# TriDrone_2012.net
KiCad netlist of a schematic drawn in EAGLE
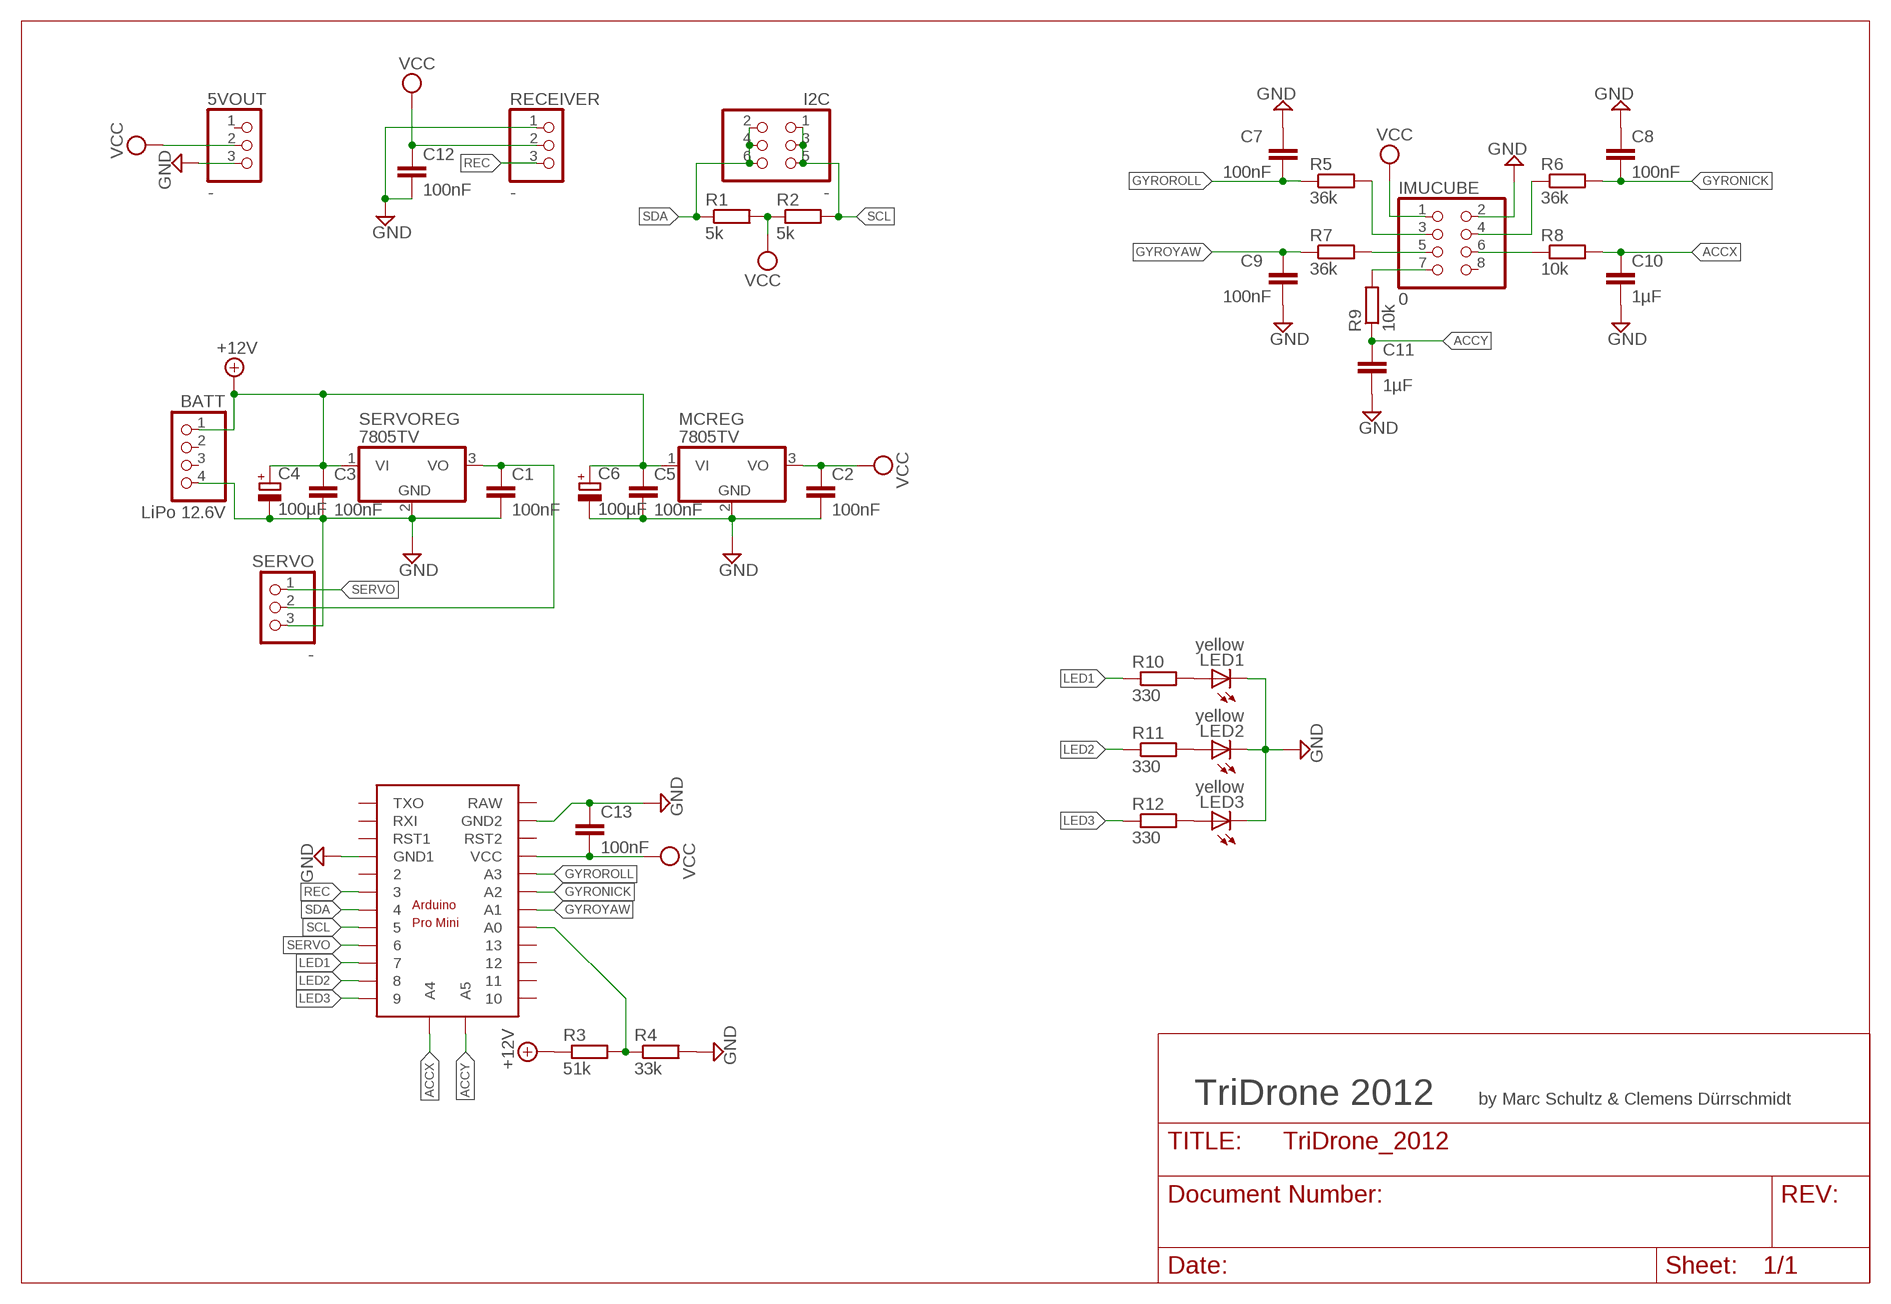
[diagram p0: schematic, sheet 1]

(export (version "E")
  (design (tool "Eeschema 10.0.6"))
  (components
    (comp (ref "5VOUT")
      (value "-")
      (footprint "eagle-import:1X03")
      (libsource (lib "eagle-import") (part "PINHD-1X3"))
    )
    (comp (ref "BATT")
      (value "LiPo 12.6V")
      (footprint "eagle-import:1X04_90")
      (libsource (lib "eagle-import") (part "PINHD-1X4/90"))
    )
    (comp (ref "C1")
      (value "100nF")
      (footprint "eagle-import:C025-025X050")
      (libsource (lib "eagle-import") (part "C-EU025-025X050"))
    )
    (comp (ref "C2")
      (value "100nF")
      (footprint "eagle-import:C025-025X050")
      (libsource (lib "eagle-import") (part "C-EU025-025X050"))
    )
    (comp (ref "C3")
      (value "100nF")
      (footprint "eagle-import:C025-025X050")
      (libsource (lib "eagle-import") (part "C-EU025-025X050"))
    )
    (comp (ref "C4")
      (value "100µF")
      (footprint "eagle-import:E2,5-7")
      (libsource (lib "eagle-import") (part "CPOL-EUE2.5-7"))
    )
    (comp (ref "C5")
      (value "100nF")
      (footprint "eagle-import:C025-025X050")
      (libsource (lib "eagle-import") (part "C-EU025-025X050"))
    )
    (comp (ref "C6")
      (value "100µF")
      (footprint "eagle-import:E2,5-7")
      (libsource (lib "eagle-import") (part "CPOL-EUE2.5-7"))
    )
    (comp (ref "C7")
      (value "100nF")
      (footprint "eagle-import:C025-025X050")
      (libsource (lib "eagle-import") (part "C-EU025-025X050"))
    )
    (comp (ref "C8")
      (value "100nF")
      (footprint "eagle-import:C025-025X050")
      (libsource (lib "eagle-import") (part "C-EU025-025X050"))
    )
    (comp (ref "C9")
      (value "100nF")
      (footprint "eagle-import:C025-025X050")
      (libsource (lib "eagle-import") (part "C-EU025-025X050"))
    )
    (comp (ref "C10")
      (value "1µF")
      (footprint "eagle-import:C025-025X050")
      (libsource (lib "eagle-import") (part "C-EU025-025X050"))
    )
    (comp (ref "C11")
      (value "1µF")
      (footprint "eagle-import:C025-025X050")
      (libsource (lib "eagle-import") (part "C-EU025-025X050"))
    )
    (comp (ref "C12")
      (value "100nF")
      (footprint "eagle-import:C025-025X050")
      (libsource (lib "eagle-import") (part "C-EU025-025X050"))
    )
    (comp (ref "C13")
      (value "100nF")
      (footprint "eagle-import:C025-025X050")
      (libsource (lib "eagle-import") (part "C-EU025-025X050"))
    )
    (comp (ref "I2C")
      (value "-")
      (footprint "eagle-import:2X03_90")
      (libsource (lib "eagle-import") (part "PINHD-2X3/90"))
    )
    (comp (ref "IMUCUBE")
      (value "0")
      (footprint "eagle-import:2X04")
      (libsource (lib "eagle-import") (part "PINHD-2X4"))
    )
    (comp (ref "LED1")
      (value "yellow")
      (footprint "eagle-import:LED3MM")
      (libsource (lib "eagle-import") (part "LED3MM"))
    )
    (comp (ref "LED2")
      (value "yellow")
      (footprint "eagle-import:LED3MM")
      (libsource (lib "eagle-import") (part "LED3MM"))
    )
    (comp (ref "LED3")
      (value "yellow")
      (footprint "eagle-import:LED3MM")
      (libsource (lib "eagle-import") (part "LED3MM"))
    )
    (comp (ref "MCREG")
      (value "7805TV")
      (footprint "eagle-import:TO220V")
      (libsource (lib "eagle-import") (part "78TV05"))
    )
    (comp (ref "R1")
      (value "5k")
      (footprint "eagle-import:0204_7")
      (libsource (lib "eagle-import") (part "R-EU_0204/7"))
    )
    (comp (ref "R2")
      (value "5k")
      (footprint "eagle-import:0204_7")
      (libsource (lib "eagle-import") (part "R-EU_0204/7"))
    )
    (comp (ref "R3")
      (value "51k")
      (footprint "eagle-import:0204_7")
      (libsource (lib "eagle-import") (part "R-EU_0204/7"))
    )
    (comp (ref "R4")
      (value "33k")
      (footprint "eagle-import:0204_7")
      (libsource (lib "eagle-import") (part "R-EU_0204/7"))
    )
    (comp (ref "R5")
      (value "36k")
      (footprint "eagle-import:0204_7")
      (libsource (lib "eagle-import") (part "R-EU_0204/7"))
    )
    (comp (ref "R6")
      (value "36k")
      (footprint "eagle-import:0204_7")
      (libsource (lib "eagle-import") (part "R-EU_0204/7"))
    )
    (comp (ref "R7")
      (value "36k")
      (footprint "eagle-import:0204_7")
      (libsource (lib "eagle-import") (part "R-EU_0204/7"))
    )
    (comp (ref "R8")
      (value "10k")
      (footprint "eagle-import:0204_7")
      (libsource (lib "eagle-import") (part "R-EU_0204/7"))
    )
    (comp (ref "R9")
      (value "10k")
      (footprint "eagle-import:0204_7")
      (libsource (lib "eagle-import") (part "R-EU_0204/7"))
    )
    (comp (ref "R10")
      (value "330")
      (footprint "eagle-import:0204_7")
      (libsource (lib "eagle-import") (part "R-EU_0204/7"))
    )
    (comp (ref "R11")
      (value "330")
      (footprint "eagle-import:0204_7")
      (libsource (lib "eagle-import") (part "R-EU_0204/7"))
    )
    (comp (ref "R12")
      (value "330")
      (footprint "eagle-import:0204_7")
      (libsource (lib "eagle-import") (part "R-EU_0204/7"))
    )
    (comp (ref "RECEIVER")
      (value "-")
      (footprint "eagle-import:1X03")
      (libsource (lib "eagle-import") (part "PINHD-1X3"))
    )
    (comp (ref "SERVO")
      (value "-")
      (footprint "eagle-import:1X03")
      (libsource (lib "eagle-import") (part "PINHD-1X3"))
    )
    (comp (ref "SERVOREG")
      (value "7805TV")
      (footprint "eagle-import:TO220V")
      (libsource (lib "eagle-import") (part "78TV05"))
    )
    (comp (ref "U$2")
      (value "ARDUINO_PRO_MINI")
      (footprint "eagle-import:ARDUINO_PRO_MINI")
      (libsource (lib "eagle-import") (part "ARDUINO_PRO_MINI"))
    )
  )
  (nets
    (net (code "1") (name "+12V") (class "Default")
      (node (ref "BATT") (pin "1") (pinfunction "1_1") (pintype "passive"))
      (node (ref "C3") (pin "1") (pinfunction "1_1") (pintype "passive"))
      (node (ref "C4") (pin "+") (pinfunction "+_+") (pintype "passive"))
      (node (ref "C5") (pin "1") (pinfunction "1_1") (pintype "passive"))
      (node (ref "C6") (pin "+") (pinfunction "+_+") (pintype "passive"))
      (node (ref "MCREG") (pin "1") (pinfunction "VI_1") (pintype "input"))
      (node (ref "R3") (pin "1") (pinfunction "1_1") (pintype "passive"))
      (node (ref "SERVOREG") (pin "1") (pinfunction "VI_1") (pintype "input"))
    )
    (net (code "2") (name "ACCX") (class "Default")
      (node (ref "C10") (pin "1") (pinfunction "1_1") (pintype "passive"))
      (node (ref "R8") (pin "2") (pinfunction "2_2") (pintype "passive"))
      (node (ref "U$2") (pin "A4") (pinfunction "A4_A4") (pintype "bidirectional"))
    )
    (net (code "3") (name "ACCY") (class "Default")
      (node (ref "C11") (pin "1") (pinfunction "1_1") (pintype "passive"))
      (node (ref "R9") (pin "1") (pinfunction "1_1") (pintype "passive"))
      (node (ref "U$2") (pin "A5") (pinfunction "A5_A5") (pintype "bidirectional"))
    )
    (net (code "4") (name "GND") (class "Default")
      (node (ref "5VOUT") (pin "3") (pinfunction "3_3") (pintype "passive"))
      (node (ref "BATT") (pin "4") (pinfunction "4_4") (pintype "passive"))
      (node (ref "C1") (pin "2") (pinfunction "2_2") (pintype "passive"))
      (node (ref "C10") (pin "2") (pinfunction "2_2") (pintype "passive"))
      (node (ref "C11") (pin "2") (pinfunction "2_2") (pintype "passive"))
      (node (ref "C12") (pin "2") (pinfunction "2_2") (pintype "passive"))
      (node (ref "C13") (pin "1") (pinfunction "1_1") (pintype "passive"))
      (node (ref "C2") (pin "2") (pinfunction "2_2") (pintype "passive"))
      (node (ref "C3") (pin "2") (pinfunction "2_2") (pintype "passive"))
      (node (ref "C4") (pin "-") (pinfunction "-_-") (pintype "passive"))
      (node (ref "C5") (pin "2") (pinfunction "2_2") (pintype "passive"))
      (node (ref "C6") (pin "-") (pinfunction "-_-") (pintype "passive"))
      (node (ref "C7") (pin "1") (pinfunction "1_1") (pintype "passive"))
      (node (ref "C8") (pin "1") (pinfunction "1_1") (pintype "passive"))
      (node (ref "C9") (pin "2") (pinfunction "2_2") (pintype "passive"))
      (node (ref "IMUCUBE") (pin "2") (pinfunction "2_2") (pintype "passive"))
      (node (ref "LED1") (pin "K") (pinfunction "C_K") (pintype "passive"))
      (node (ref "LED2") (pin "K") (pinfunction "C_K") (pintype "passive"))
      (node (ref "LED3") (pin "K") (pinfunction "C_K") (pintype "passive"))
      (node (ref "MCREG") (pin "2") (pinfunction "GND_2") (pintype "passive"))
      (node (ref "R4") (pin "2") (pinfunction "2_2") (pintype "passive"))
      (node (ref "RECEIVER") (pin "1") (pinfunction "1_1") (pintype "passive"))
      (node (ref "SERVO") (pin "3") (pinfunction "3_3") (pintype "passive"))
      (node (ref "SERVOREG") (pin "2") (pinfunction "GND_2") (pintype "passive"))
      (node (ref "U$2") (pin "GND1") (pinfunction "GND1_GND1") (pintype "bidirectional"))
      (node (ref "U$2") (pin "GND2") (pinfunction "GND2_GND2") (pintype "bidirectional"))
    )
    (net (code "5") (name "GYRONICK") (class "Default")
      (node (ref "C8") (pin "2") (pinfunction "2_2") (pintype "passive"))
      (node (ref "R6") (pin "2") (pinfunction "2_2") (pintype "passive"))
      (node (ref "U$2") (pin "A2") (pinfunction "A2_A2") (pintype "bidirectional"))
    )
    (net (code "6") (name "GYROROLL") (class "Default")
      (node (ref "C7") (pin "2") (pinfunction "2_2") (pintype "passive"))
      (node (ref "R5") (pin "1") (pinfunction "1_1") (pintype "passive"))
      (node (ref "U$2") (pin "A3") (pinfunction "A3_A3") (pintype "bidirectional"))
    )
    (net (code "7") (name "GYROYAW") (class "Default")
      (node (ref "C9") (pin "1") (pinfunction "1_1") (pintype "passive"))
      (node (ref "R7") (pin "1") (pinfunction "1_1") (pintype "passive"))
      (node (ref "U$2") (pin "A1") (pinfunction "A1_A1") (pintype "bidirectional"))
    )
    (net (code "8") (name "LED1") (class "Default")
      (node (ref "R10") (pin "1") (pinfunction "1_1") (pintype "passive"))
      (node (ref "U$2") (pin "7") (pinfunction "7_7") (pintype "bidirectional"))
    )
    (net (code "9") (name "LED2") (class "Default")
      (node (ref "R11") (pin "1") (pinfunction "1_1") (pintype "passive"))
      (node (ref "U$2") (pin "8") (pinfunction "8_8") (pintype "bidirectional"))
    )
    (net (code "10") (name "LED3") (class "Default")
      (node (ref "R12") (pin "1") (pinfunction "1_1") (pintype "passive"))
      (node (ref "U$2") (pin "9") (pinfunction "9_9") (pintype "bidirectional"))
    )
    (net (code "11") (name "Net-(IMUCUBE-Pad3)") (class "Default")
      (node (ref "IMUCUBE") (pin "3") (pinfunction "3_3") (pintype "passive"))
      (node (ref "R5") (pin "2") (pinfunction "2_2") (pintype "passive"))
    )
    (net (code "12") (name "Net-(IMUCUBE-Pad4)") (class "Default")
      (node (ref "IMUCUBE") (pin "4") (pinfunction "4_4") (pintype "passive"))
      (node (ref "R6") (pin "1") (pinfunction "1_1") (pintype "passive"))
    )
    (net (code "13") (name "Net-(IMUCUBE-Pad5)") (class "Default")
      (node (ref "IMUCUBE") (pin "5") (pinfunction "5_5") (pintype "passive"))
      (node (ref "R7") (pin "2") (pinfunction "2_2") (pintype "passive"))
    )
    (net (code "14") (name "Net-(IMUCUBE-Pad6)") (class "Default")
      (node (ref "IMUCUBE") (pin "6") (pinfunction "6_6") (pintype "passive"))
      (node (ref "R8") (pin "1") (pinfunction "1_1") (pintype "passive"))
    )
    (net (code "15") (name "Net-(IMUCUBE-Pad7)") (class "Default")
      (node (ref "IMUCUBE") (pin "7") (pinfunction "7_7") (pintype "passive"))
      (node (ref "R9") (pin "2") (pinfunction "2_2") (pintype "passive"))
    )
    (net (code "16") (name "Net-(LED1-PadA)") (class "Default")
      (node (ref "LED1") (pin "A") (pinfunction "A_A") (pintype "passive"))
      (node (ref "R10") (pin "2") (pinfunction "2_2") (pintype "passive"))
    )
    (net (code "17") (name "Net-(LED2-PadA)") (class "Default")
      (node (ref "LED2") (pin "A") (pinfunction "A_A") (pintype "passive"))
      (node (ref "R11") (pin "2") (pinfunction "2_2") (pintype "passive"))
    )
    (net (code "18") (name "Net-(LED3-PadA)") (class "Default")
      (node (ref "LED3") (pin "A") (pinfunction "A_A") (pintype "passive"))
      (node (ref "R12") (pin "2") (pinfunction "2_2") (pintype "passive"))
    )
    (net (code "19") (name "Net-(R3-Pad2)") (class "Default")
      (node (ref "R3") (pin "2") (pinfunction "2_2") (pintype "passive"))
      (node (ref "R4") (pin "1") (pinfunction "1_1") (pintype "passive"))
      (node (ref "U$2") (pin "A0") (pinfunction "A0_A0") (pintype "bidirectional"))
    )
    (net (code "20") (name "Net-(SERVOREG-VO)") (class "Default")
      (node (ref "C1") (pin "1") (pinfunction "1_1") (pintype "passive"))
      (node (ref "SERVO") (pin "2") (pinfunction "2_2") (pintype "passive"))
      (node (ref "SERVOREG") (pin "3") (pinfunction "VO_3") (pintype "passive"))
    )
    (net (code "21") (name "REC") (class "Default")
      (node (ref "RECEIVER") (pin "3") (pinfunction "3_3") (pintype "passive"))
      (node (ref "U$2") (pin "3") (pinfunction "3_3") (pintype "bidirectional"))
    )
    (net (code "22") (name "SCL") (class "Default")
      (node (ref "I2C") (pin "1") (pinfunction "1_1") (pintype "passive"))
      (node (ref "I2C") (pin "3") (pinfunction "3_3") (pintype "passive"))
      (node (ref "I2C") (pin "5") (pinfunction "5_5") (pintype "passive"))
      (node (ref "R2") (pin "2") (pinfunction "2_2") (pintype "passive"))
      (node (ref "U$2") (pin "5") (pinfunction "5_5") (pintype "bidirectional"))
    )
    (net (code "23") (name "SDA") (class "Default")
      (node (ref "I2C") (pin "2") (pinfunction "2_2") (pintype "passive"))
      (node (ref "I2C") (pin "4") (pinfunction "4_4") (pintype "passive"))
      (node (ref "I2C") (pin "6") (pinfunction "6_6") (pintype "passive"))
      (node (ref "R1") (pin "1") (pinfunction "1_1") (pintype "passive"))
      (node (ref "U$2") (pin "4") (pinfunction "4_4") (pintype "bidirectional"))
    )
    (net (code "24") (name "SERVO") (class "Default")
      (node (ref "SERVO") (pin "1") (pinfunction "1_1") (pintype "passive"))
      (node (ref "U$2") (pin "6") (pinfunction "6_6") (pintype "bidirectional"))
    )
    (net (code "25") (name "VCC") (class "Default")
      (node (ref "5VOUT") (pin "2") (pinfunction "2_2") (pintype "passive"))
      (node (ref "C12") (pin "1") (pinfunction "1_1") (pintype "passive"))
      (node (ref "C13") (pin "2") (pinfunction "2_2") (pintype "passive"))
      (node (ref "C2") (pin "1") (pinfunction "1_1") (pintype "passive"))
      (node (ref "IMUCUBE") (pin "1") (pinfunction "1_1") (pintype "passive"))
      (node (ref "MCREG") (pin "3") (pinfunction "VO_3") (pintype "passive"))
      (node (ref "R1") (pin "2") (pinfunction "2_2") (pintype "passive"))
      (node (ref "R2") (pin "1") (pinfunction "1_1") (pintype "passive"))
      (node (ref "RECEIVER") (pin "2") (pinfunction "2_2") (pintype "passive"))
      (node (ref "U$2") (pin "VCC") (pinfunction "VCC_VCC") (pintype "bidirectional"))
    )
    (net (code "26") (name "unconnected-(5VOUT-Pad1)") (class "Default")
      (node (ref "5VOUT") (pin "1") (pinfunction "1_1") (pintype "passive"))
    )
    (net (code "27") (name "unconnected-(BATT-Pad2)") (class "Default")
      (node (ref "BATT") (pin "2") (pinfunction "2_2") (pintype "passive"))
    )
    (net (code "28") (name "unconnected-(BATT-Pad3)") (class "Default")
      (node (ref "BATT") (pin "3") (pinfunction "3_3") (pintype "passive"))
    )
    (net (code "29") (name "unconnected-(IMUCUBE-Pad8)") (class "Default")
      (node (ref "IMUCUBE") (pin "8") (pinfunction "8_8") (pintype "passive"))
    )
    (net (code "30") (name "unconnected-(U$2-Pad2)") (class "Default")
      (node (ref "U$2") (pin "2") (pinfunction "2_2") (pintype "bidirectional"))
    )
    (net (code "31") (name "unconnected-(U$2-Pad10)") (class "Default")
      (node (ref "U$2") (pin "10") (pinfunction "10_10") (pintype "bidirectional"))
    )
    (net (code "32") (name "unconnected-(U$2-Pad11)") (class "Default")
      (node (ref "U$2") (pin "11") (pinfunction "11_11") (pintype "bidirectional"))
    )
    (net (code "33") (name "unconnected-(U$2-Pad12)") (class "Default")
      (node (ref "U$2") (pin "12") (pinfunction "12_12") (pintype "bidirectional"))
    )
    (net (code "34") (name "unconnected-(U$2-Pad13)") (class "Default")
      (node (ref "U$2") (pin "13") (pinfunction "13_13") (pintype "bidirectional"))
    )
    (net (code "35") (name "unconnected-(U$2-PadRAW)") (class "Default")
      (node (ref "U$2") (pin "RAW") (pinfunction "RAW_RAW") (pintype "bidirectional"))
    )
    (net (code "36") (name "unconnected-(U$2-PadRST1)") (class "Default")
      (node (ref "U$2") (pin "RST1") (pinfunction "RST1_RST1") (pintype "bidirectional"))
    )
    (net (code "37") (name "unconnected-(U$2-PadRST2)") (class "Default")
      (node (ref "U$2") (pin "RST2") (pinfunction "RST2_RST2") (pintype "bidirectional"))
    )
    (net (code "38") (name "unconnected-(U$2-PadRXI)") (class "Default")
      (node (ref "U$2") (pin "RXI") (pinfunction "RXI_RXI") (pintype "bidirectional"))
    )
    (net (code "39") (name "unconnected-(U$2-PadTXO)") (class "Default")
      (node (ref "U$2") (pin "TXO") (pinfunction "TXO_TXO") (pintype "output"))
    )
  )
)
